# 2-bot_1b.net
KiCad netlist of a schematic drawn in Altium Designer
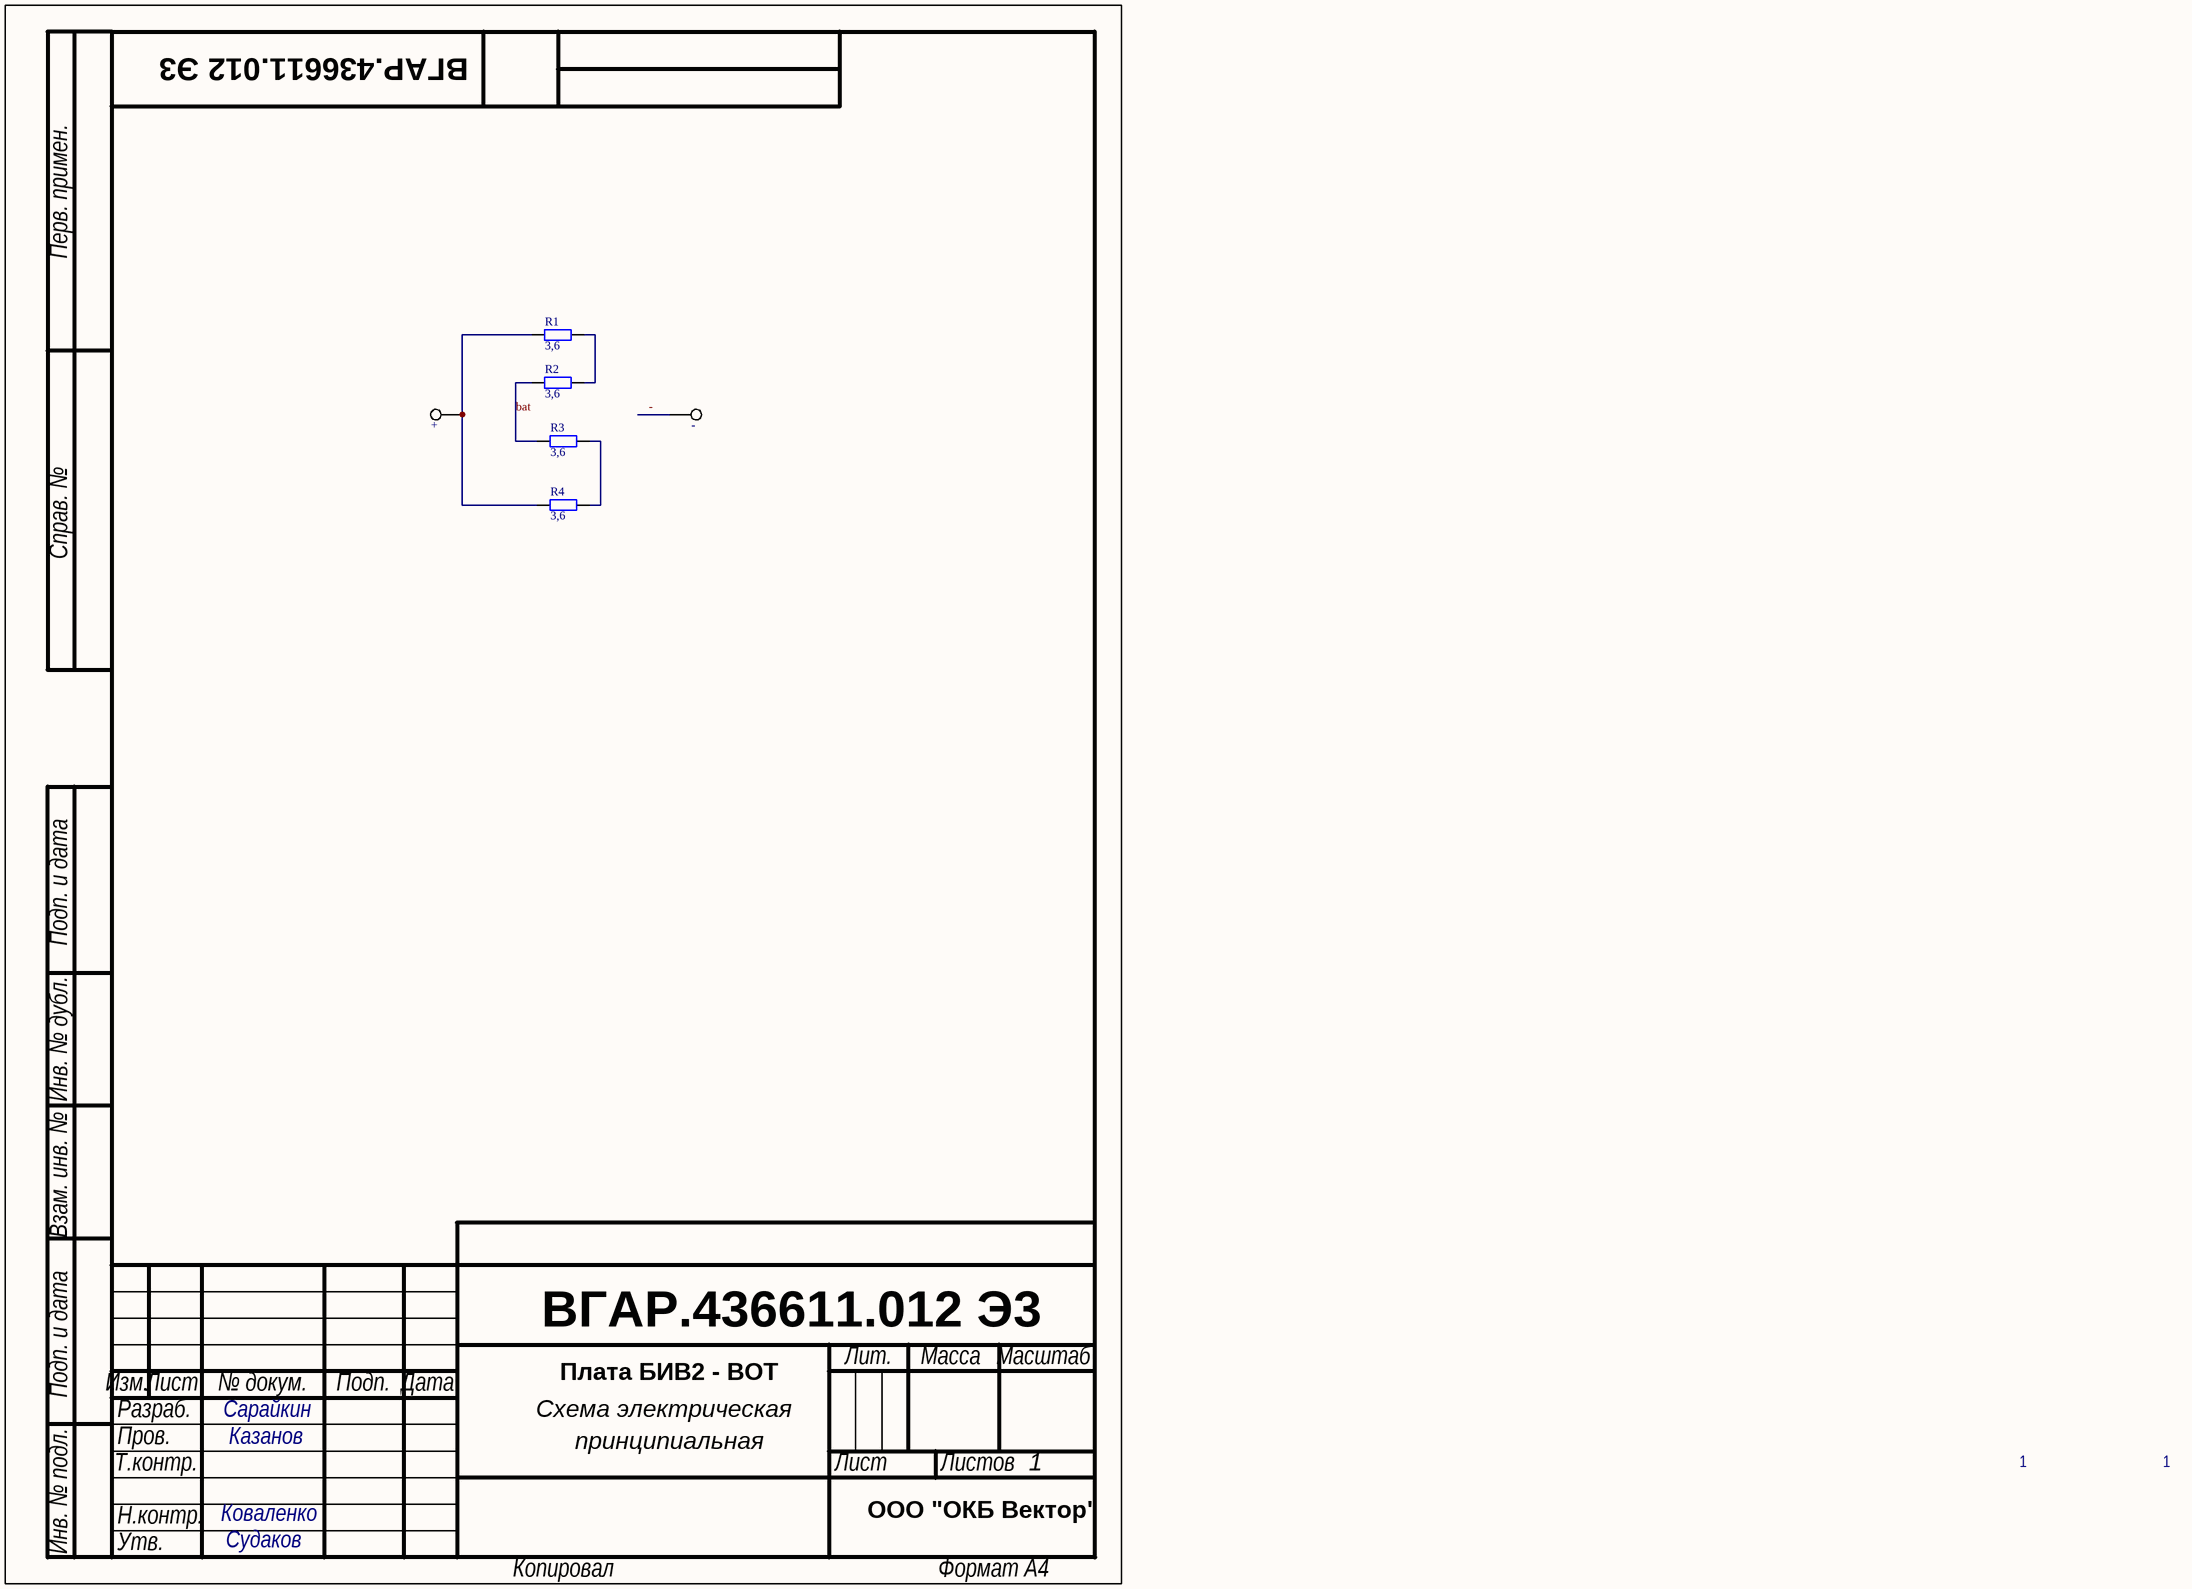
[diagram p0: бив2-bot_1b.SchDoc]

(export (version "E")
  (design (tool "Eeschema 10.0.6"))
  (components
    (comp (ref "+")
      (value "Testpoint-TH-1.5mm")
      (footprint "1.5mm PAD")
      (description "Dummy Pad")
      (libsource (lib "Board Level Debug Tools") (part "Testpoint-TH-1.5mm"))
    )
    (comp (ref "-")
      (value "Testpoint-TH-1.5mm")
      (footprint "1.5mm PAD")
      (description "Dummy Pad")
      (libsource (lib "Board Level Debug Tools") (part "Testpoint-TH-1.5mm"))
    )
    (comp (ref "R1")
      (value "3,6")
      (footprint "RESC6432(2512)X06L")
      (description "Резистор")
      (fields (field (name "MANUFACTURER") "Bourns") (field (name "POWER") "1 Вт"))
      (libsource (lib "Chip Resistor") (part "R2512L"))
    )
    (comp (ref "R2")
      (value "3,6")
      (footprint "RESC6432(2512)X06L")
      (description "Резистор")
      (fields (field (name "MANUFACTURER") "Bourns") (field (name "POWER") "1 Вт"))
      (libsource (lib "Chip Resistor") (part "R2512L"))
    )
    (comp (ref "R3")
      (value "3,6")
      (footprint "RESC6432(2512)X06L")
      (description "Резистор")
      (fields (field (name "MANUFACTURER") "Bourns") (field (name "POWER") "1 Вт"))
      (libsource (lib "Chip Resistor") (part "R2512L"))
    )
    (comp (ref "R4")
      (value "3,6")
      (footprint "RESC6432(2512)X06L")
      (description "Резистор")
      (fields (field (name "MANUFACTURER") "Bourns") (field (name "POWER") "1 Вт"))
      (libsource (lib "Chip Resistor") (part "R2512L"))
    )
  )
  (nets
    (net (code "1") (name "/-") (class "Default")
      (node (ref "-") (pin "0") (pinfunction "0_0") (pintype "passive"))
    )
    (net (code "2") (name "/bat") (class "Default")
      (node (ref "R2") (pin "1") (pinfunction "1_1") (pintype "passive"))
      (node (ref "R3") (pin "1") (pinfunction "1_1") (pintype "passive"))
    )
    (net (code "3") (name "Net-(+-Pad0)") (class "Default")
      (node (ref "+") (pin "0") (pinfunction "0_0") (pintype "passive"))
      (node (ref "R1") (pin "1") (pinfunction "1_1") (pintype "passive"))
      (node (ref "R4") (pin "1") (pinfunction "1_1") (pintype "passive"))
    )
    (net (code "4") (name "Net-(R1-Pad2)") (class "Default")
      (node (ref "R1") (pin "2") (pinfunction "2_2") (pintype "passive"))
      (node (ref "R2") (pin "2") (pinfunction "2_2") (pintype "passive"))
    )
    (net (code "5") (name "Net-(R3-Pad2)") (class "Default")
      (node (ref "R3") (pin "2") (pinfunction "2_2") (pintype "passive"))
      (node (ref "R4") (pin "2") (pinfunction "2_2") (pintype "passive"))
    )
  )
)
